# ICSL_PS_Combined_BMD.net
KiCad netlist of a schematic drawn in Altium Designer
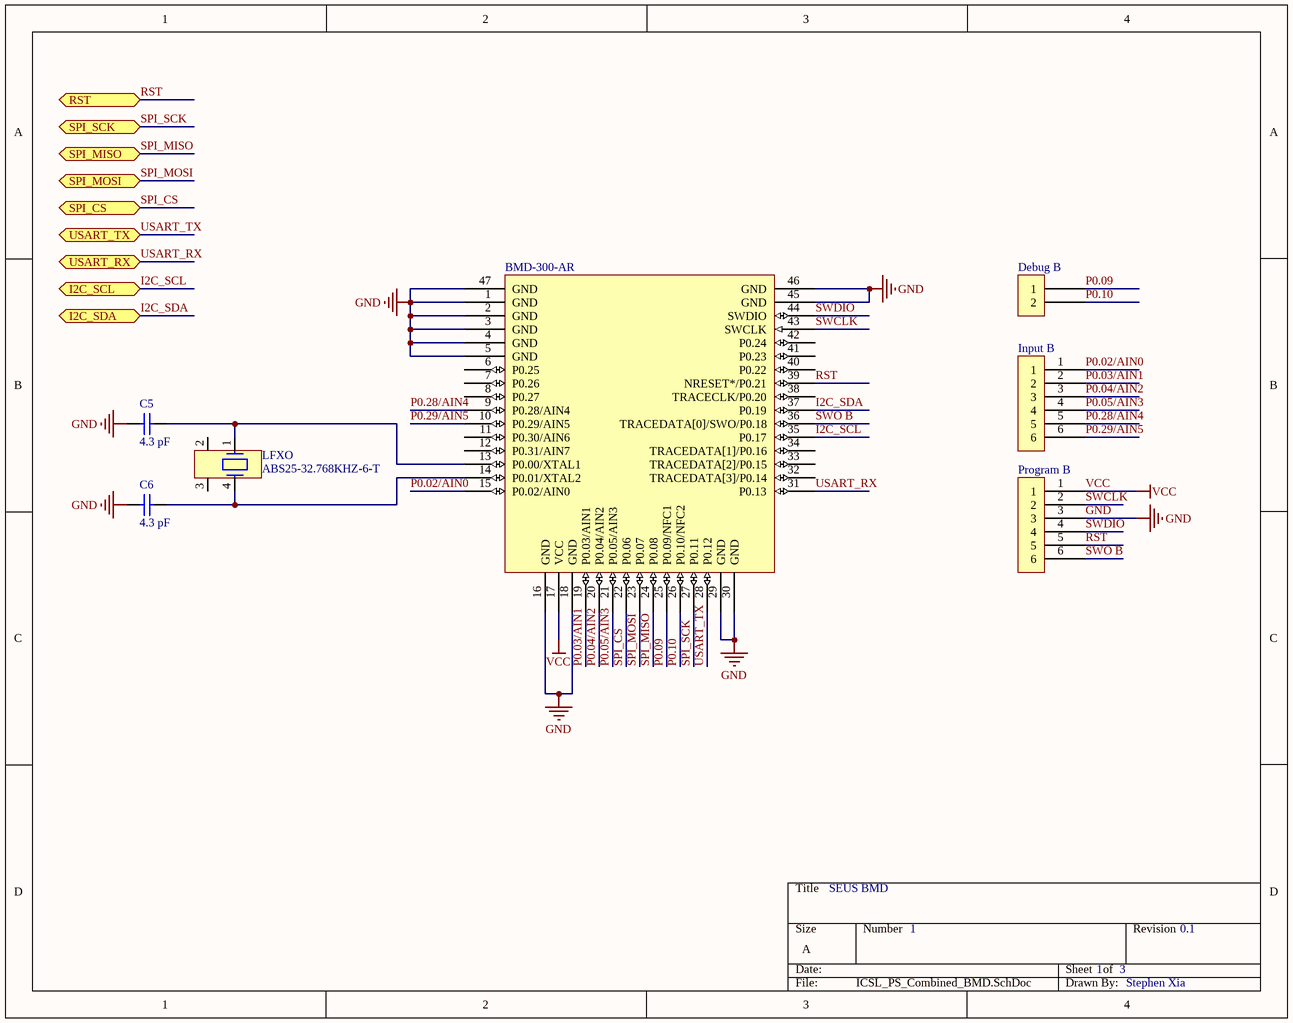
[diagram p0: ICSL_PS_Combined_BMD.SchDoc]

(export (version "E")
  (design (tool "Eeschema 10.0.6"))
  (components
    (comp (ref "BMD-300-AR")
      (value "Rigado BMD-300-A-R")
      (footprint "BMD-300 easy")
      (description "Mod Ble 4.2 Nordic Nrf52832 Soc")
      (fields (field (name "MANUFACTURER PART NUMBER") "BMD-300-A-R"))
      (libsource (lib "Octopart library") (part "BMD-300"))
    )
    (comp (ref "C5")
      (value "4.3 pF")
      (footprint "CAPC1608X87X35LL15T15")
      (description "Multilayer Ceramic Capacitors MLCC - SMD/SMT 50volts 82000pF X7R 10%")
      (libsource (lib "Octopart library") (part "CAP-2"))
    )
    (comp (ref "C6")
      (value "4.3 pF")
      (footprint "CAPC1608X87X35LL15T15")
      (description "Multilayer Ceramic Capacitors MLCC - SMD/SMT 50volts 82000pF X7R 10%")
      (libsource (lib "Octopart library") (part "CAP-2"))
    )
    (comp (ref "Debug B")
      (value "TE Connectivity / AMP 3-644695-2")
      (footprint "PCB-i8m17woc8q0u0fbeoczf-1")
      (description "Connector Unshrouded Header 2 Position 2.54mm Solder Straight Thru-Hole")
      (fields (field (name "MANUFACTURER PART NUMBER") "3-644695-2"))
      (libsource (lib "Octopart library") (part "SYM-2792ecc2f21af855-1"))
    )
    (comp (ref "Input B")
      (value "TE Connectivity / AMP 5-146281-6")
      (footprint "PCB-ceua2d6kgzjhmbkiz2sm-1")
      (description "Header; Breakaway; 0.100 in.; PC Board; Single; 6; 0.025 in.; 0.12 in.; 3 A")
      (fields (field (name "MANUFACTURER PART NUMBER") "5-146281-2"))
      (libsource (lib "Octopart library") (part "SYM-4f28847cfb2a90ef-1"))
    )
    (comp (ref "LFXO")
      (value "ABS25-32.768KHZ-6-T")
      (footprint "XTAL_4SM_8X3R8")
      (description "ABS25 Series 32.768 kHz ±20 ppm 6 pF -40 to +85 °C SMT Low Frequency Crystal")
      (libsource (lib "CommunityVault") (part "XTAL_4P-4"))
    )
    (comp (ref "Program B")
      (value "TE Connectivity / AMP 5-146281-6")
      (footprint "PCB-ceua2d6kgzjhmbkiz2sm-1")
      (description "Header; Breakaway; 0.100 in.; PC Board; Single; 6; 0.025 in.; 0.12 in.; 3 A")
      (fields (field (name "MANUFACTURER PART NUMBER") "5-146281-2"))
      (libsource (lib "Octopart library") (part "SYM-4f28847cfb2a90ef-1"))
    )
  )
  (nets
    (net (code "1") (name "/I2C_SCL") (class "Default")
      (node (ref "BMD-300-AR") (pin "35") (pinfunction "P0.17_35") (pintype "bidirectional"))
    )
    (net (code "2") (name "/I2C_SDA") (class "Default")
      (node (ref "BMD-300-AR") (pin "37") (pinfunction "P0.19_37") (pintype "bidirectional"))
    )
    (net (code "3") (name "/P0.02{slash}AIN0") (class "Default")
      (node (ref "BMD-300-AR") (pin "15") (pinfunction "P0.02/AIN0_15") (pintype "bidirectional"))
      (node (ref "Input B") (pin "1") (pinfunction "1_1") (pintype "passive"))
    )
    (net (code "4") (name "/P0.03{slash}AIN1") (class "Default")
      (node (ref "BMD-300-AR") (pin "19") (pinfunction "P0.03/AIN1_19") (pintype "bidirectional"))
      (node (ref "Input B") (pin "2") (pinfunction "2_2") (pintype "passive"))
    )
    (net (code "5") (name "/P0.04{slash}AIN2") (class "Default")
      (node (ref "BMD-300-AR") (pin "20") (pinfunction "P0.04/AIN2_20") (pintype "bidirectional"))
      (node (ref "Input B") (pin "3") (pinfunction "3_3") (pintype "passive"))
    )
    (net (code "6") (name "/P0.05{slash}AIN3") (class "Default")
      (node (ref "BMD-300-AR") (pin "21") (pinfunction "P0.05/AIN3_21") (pintype "bidirectional"))
      (node (ref "Input B") (pin "4") (pinfunction "4_4") (pintype "passive"))
    )
    (net (code "7") (name "/P0.09") (class "Default")
      (node (ref "BMD-300-AR") (pin "25") (pinfunction "P0.09/NFC1_25") (pintype "bidirectional"))
      (node (ref "Debug B") (pin "1") (pinfunction "1_1") (pintype "passive"))
    )
    (net (code "8") (name "/P0.10") (class "Default")
      (node (ref "BMD-300-AR") (pin "26") (pinfunction "P0.10/NFC2_26") (pintype "bidirectional"))
      (node (ref "Debug B") (pin "2") (pinfunction "2_2") (pintype "passive"))
    )
    (net (code "9") (name "/P0.28{slash}AIN4") (class "Default")
      (node (ref "BMD-300-AR") (pin "9") (pinfunction "P0.28/AIN4_9") (pintype "bidirectional"))
      (node (ref "Input B") (pin "5") (pinfunction "5_5") (pintype "passive"))
    )
    (net (code "10") (name "/P0.29{slash}AIN5") (class "Default")
      (node (ref "BMD-300-AR") (pin "10") (pinfunction "P0.29/AIN5_10") (pintype "bidirectional"))
      (node (ref "Input B") (pin "6") (pinfunction "6_6") (pintype "passive"))
    )
    (net (code "11") (name "/RST") (class "Default")
      (node (ref "BMD-300-AR") (pin "39") (pinfunction "NRESET*/P0.21_39") (pintype "bidirectional"))
      (node (ref "Program B") (pin "5") (pinfunction "5_5") (pintype "passive"))
    )
    (net (code "12") (name "/SPI_CS") (class "Default")
      (node (ref "BMD-300-AR") (pin "22") (pinfunction "P0.06_22") (pintype "bidirectional"))
    )
    (net (code "13") (name "/SPI_MISO") (class "Default")
      (node (ref "BMD-300-AR") (pin "24") (pinfunction "P0.08_24") (pintype "bidirectional"))
    )
    (net (code "14") (name "/SPI_MOSI") (class "Default")
      (node (ref "BMD-300-AR") (pin "23") (pinfunction "P0.07_23") (pintype "bidirectional"))
    )
    (net (code "15") (name "/SPI_SCK") (class "Default")
      (node (ref "BMD-300-AR") (pin "27") (pinfunction "P0.11_27") (pintype "bidirectional"))
    )
    (net (code "16") (name "/SWCLK") (class "Default")
      (node (ref "BMD-300-AR") (pin "43") (pinfunction "SWCLK_43") (pintype "input"))
      (node (ref "Program B") (pin "2") (pinfunction "2_2") (pintype "passive"))
    )
    (net (code "17") (name "/SWDIO") (class "Default")
      (node (ref "BMD-300-AR") (pin "44") (pinfunction "SWDIO_44") (pintype "bidirectional"))
      (node (ref "Program B") (pin "4") (pinfunction "4_4") (pintype "passive"))
    )
    (net (code "18") (name "/SWO B") (class "Default")
      (node (ref "BMD-300-AR") (pin "36") (pinfunction "TRACEDATA[0]/SWO/P0.18_36") (pintype "bidirectional"))
      (node (ref "Program B") (pin "6") (pinfunction "6_6") (pintype "passive"))
    )
    (net (code "19") (name "/USART_RX") (class "Default")
      (node (ref "BMD-300-AR") (pin "31") (pinfunction "P0.13_31") (pintype "bidirectional"))
    )
    (net (code "20") (name "/USART_TX") (class "Default")
      (node (ref "BMD-300-AR") (pin "28") (pinfunction "P0.12_28") (pintype "bidirectional"))
    )
    (net (code "21") (name "GND") (class "Default")
      (node (ref "BMD-300-AR") (pin "1") (pinfunction "GND_1") (pintype "power_in"))
      (node (ref "BMD-300-AR") (pin "16") (pinfunction "GND_16") (pintype "power_in"))
      (node (ref "BMD-300-AR") (pin "18") (pinfunction "GND_18") (pintype "power_in"))
      (node (ref "BMD-300-AR") (pin "2") (pinfunction "GND_2") (pintype "power_in"))
      (node (ref "BMD-300-AR") (pin "29") (pinfunction "GND_29") (pintype "power_in"))
      (node (ref "BMD-300-AR") (pin "3") (pinfunction "GND_3") (pintype "power_in"))
      (node (ref "BMD-300-AR") (pin "30") (pinfunction "GND_30") (pintype "power_in"))
      (node (ref "BMD-300-AR") (pin "4") (pinfunction "GND_4") (pintype "power_in"))
      (node (ref "BMD-300-AR") (pin "45") (pinfunction "GND_45") (pintype "power_in"))
      (node (ref "BMD-300-AR") (pin "46") (pinfunction "GND_46") (pintype "power_in"))
      (node (ref "BMD-300-AR") (pin "47") (pinfunction "GND_47") (pintype "power_in"))
      (node (ref "BMD-300-AR") (pin "5") (pinfunction "GND_5") (pintype "power_in"))
      (node (ref "C5") (pin "1") (pinfunction "1_1") (pintype "passive"))
      (node (ref "C6") (pin "1") (pinfunction "1_1") (pintype "passive"))
      (node (ref "Program B") (pin "3") (pinfunction "3_3") (pintype "passive"))
    )
    (net (code "22") (name "Net-(BMD-300-AR-P0.00{slash}XTAL1)") (class "Default")
      (node (ref "BMD-300-AR") (pin "13") (pinfunction "P0.00/XTAL1_13") (pintype "bidirectional"))
      (node (ref "C5") (pin "2") (pinfunction "2_2") (pintype "passive"))
      (node (ref "LFXO") (pin "1") (pinfunction "1_1") (pintype "passive"))
    )
    (net (code "23") (name "Net-(BMD-300-AR-P0.01{slash}XTAL2)") (class "Default")
      (node (ref "BMD-300-AR") (pin "14") (pinfunction "P0.01/XTAL2_14") (pintype "bidirectional"))
      (node (ref "C6") (pin "2") (pinfunction "2_2") (pintype "passive"))
      (node (ref "LFXO") (pin "4") (pinfunction "4_4") (pintype "passive"))
    )
    (net (code "24") (name "VCC") (class "Default")
      (node (ref "BMD-300-AR") (pin "17") (pinfunction "VCC_17") (pintype "power_in"))
      (node (ref "Program B") (pin "1") (pinfunction "1_1") (pintype "passive"))
    )
    (net (code "25") (name "unconnected-(BMD-300-AR-P0.22-Pad40)") (class "Default")
      (node (ref "BMD-300-AR") (pin "40") (pinfunction "P0.22_40") (pintype "bidirectional"))
    )
    (net (code "26") (name "unconnected-(BMD-300-AR-P0.23-Pad41)") (class "Default")
      (node (ref "BMD-300-AR") (pin "41") (pinfunction "P0.23_41") (pintype "bidirectional"))
    )
    (net (code "27") (name "unconnected-(BMD-300-AR-P0.24-Pad42)") (class "Default")
      (node (ref "BMD-300-AR") (pin "42") (pinfunction "P0.24_42") (pintype "bidirectional"))
    )
    (net (code "28") (name "unconnected-(BMD-300-AR-P0.25-Pad6)") (class "Default")
      (node (ref "BMD-300-AR") (pin "6") (pinfunction "P0.25_6") (pintype "bidirectional"))
    )
    (net (code "29") (name "unconnected-(BMD-300-AR-P0.26-Pad7)") (class "Default")
      (node (ref "BMD-300-AR") (pin "7") (pinfunction "P0.26_7") (pintype "bidirectional"))
    )
    (net (code "30") (name "unconnected-(BMD-300-AR-P0.27-Pad8)") (class "Default")
      (node (ref "BMD-300-AR") (pin "8") (pinfunction "P0.27_8") (pintype "bidirectional"))
    )
    (net (code "31") (name "unconnected-(BMD-300-AR-P0.30{slash}AIN6-Pad11)") (class "Default")
      (node (ref "BMD-300-AR") (pin "11") (pinfunction "P0.30/AIN6_11") (pintype "bidirectional"))
    )
    (net (code "32") (name "unconnected-(BMD-300-AR-P0.31{slash}AIN7-Pad12)") (class "Default")
      (node (ref "BMD-300-AR") (pin "12") (pinfunction "P0.31/AIN7_12") (pintype "bidirectional"))
    )
    (net (code "33") (name "unconnected-(BMD-300-AR-TRACECLK{slash}P0.20-Pad38)") (class "Default")
      (node (ref "BMD-300-AR") (pin "38") (pinfunction "TRACECLK/P0.20_38") (pintype "bidirectional"))
    )
    (net (code "34") (name "unconnected-(BMD-300-AR-TRACEDATA[1]{slash}P0.16-Pad34)") (class "Default")
      (node (ref "BMD-300-AR") (pin "34") (pinfunction "TRACEDATA[1]/P0.16_34") (pintype "bidirectional"))
    )
    (net (code "35") (name "unconnected-(BMD-300-AR-TRACEDATA[2]{slash}P0.15-Pad33)") (class "Default")
      (node (ref "BMD-300-AR") (pin "33") (pinfunction "TRACEDATA[2]/P0.15_33") (pintype "bidirectional"))
    )
    (net (code "36") (name "unconnected-(BMD-300-AR-TRACEDATA[3]{slash}P0.14-Pad32)") (class "Default")
      (node (ref "BMD-300-AR") (pin "32") (pinfunction "TRACEDATA[3]/P0.14_32") (pintype "bidirectional"))
    )
    (net (code "37") (name "unconnected-(LFXO-Pad2)") (class "Default")
      (node (ref "LFXO") (pin "2") (pinfunction "2_2") (pintype "passive"))
    )
    (net (code "38") (name "unconnected-(LFXO-Pad3)") (class "Default")
      (node (ref "LFXO") (pin "3") (pinfunction "3_3") (pintype "passive"))
    )
  )
)
